# ProPrj.net
KiCad netlist of a schematic drawn in EasyEDA Pro
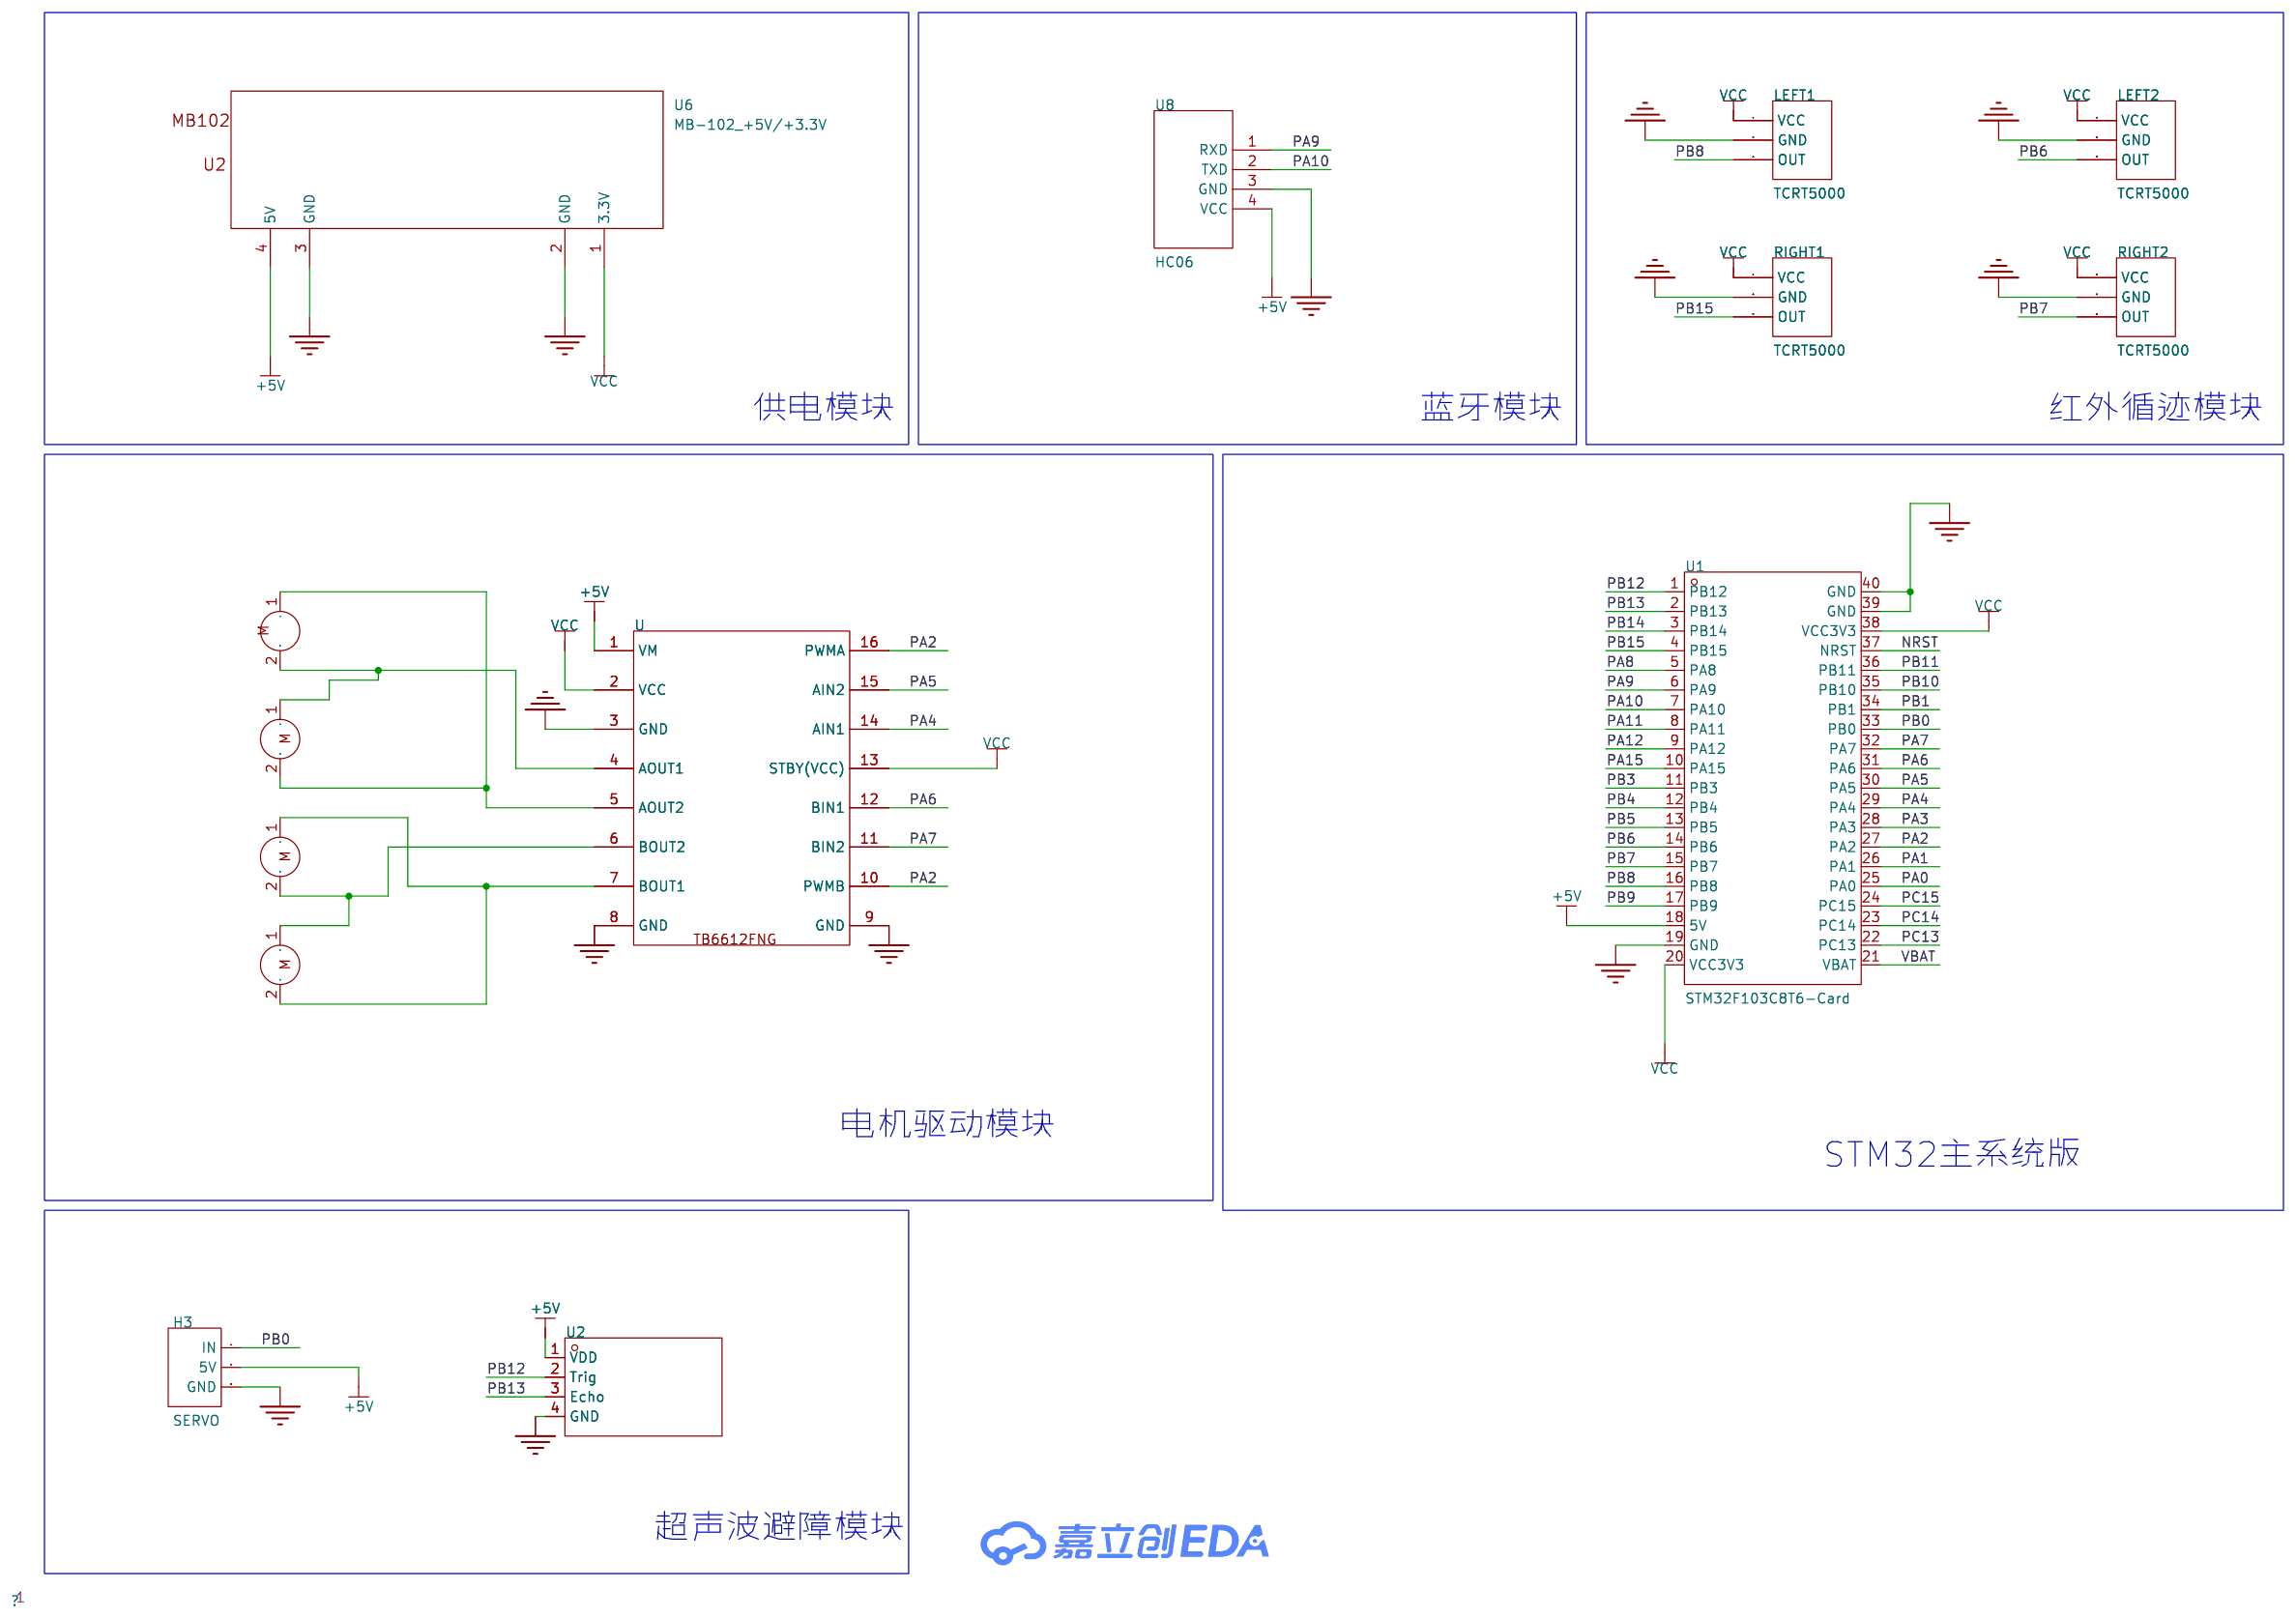
[diagram p0: schematic sheet]

(export (version "E")
  (design (tool "Eeschema 10.0.6"))
  (components
    (comp (ref "H3")
      (value "SERVO")
      (footprint "easyedapro:SERVO")
      (fields (field (name "Manufacturer Part") "Header2.54mm 1*3P") (field (name "Manufacturer") "BOOMELE"))
      (libsource (lib "easyedapro") (part "SERVO"))
    )
    (comp (ref "LEFT1")
      (value "TCRT5000")
      (footprint "easyedapro:footprint_0961")
      (libsource (lib "easyedapro") (part "TCRT5000"))
    )
    (comp (ref "LEFT2")
      (value "TCRT5000")
      (footprint "easyedapro:footprint_0961")
      (libsource (lib "easyedapro") (part "TCRT5000"))
    )
    (comp (ref "LEFT3")
      (value "DC 12V")
      (footprint "easyedapro:电源端子-2P")
      (libsource (lib "easyedapro") (part "直流电机"))
    )
    (comp (ref "LEFT4")
      (value "DC 12V")
      (footprint "easyedapro:电源端子-2P")
      (libsource (lib "easyedapro") (part "直流电机"))
    )
    (comp (ref "RIGHT1")
      (value "TCRT5000")
      (footprint "easyedapro:footprint_0961")
      (libsource (lib "easyedapro") (part "TCRT5000"))
    )
    (comp (ref "RIGHT2")
      (value "TCRT5000")
      (footprint "easyedapro:footprint_0961")
      (libsource (lib "easyedapro") (part "TCRT5000"))
    )
    (comp (ref "RIGHT3")
      (value "DC 12V")
      (footprint "easyedapro:电源端子-2P")
      (libsource (lib "easyedapro") (part "直流电机"))
    )
    (comp (ref "RIGHT4")
      (value "DC 12V")
      (footprint "easyedapro:电源端子-2P")
      (libsource (lib "easyedapro") (part "直流电机"))
    )
    (comp (ref "U")
      (value "~")
      (footprint "easyedapro:TB6612FNG")
      (libsource (lib "easyedapro") (part "TB6612"))
    )
    (comp (ref "U1")
      (value "STM32F103C8T6-Card")
      (footprint "easyedapro:CONN-TH_L53.3-W22.9_STM32F103C8T6-CARD")
      (libsource (lib "easyedapro") (part "STM32F103C8T6-CARD"))
    )
    (comp (ref "U2")
      (value "~")
      (footprint "easyedapro:HC-SR04")
      (libsource (lib "easyedapro") (part "HC-SR04"))
    )
    (comp (ref "U6")
      (value "MB-102_+5V/+3.3V")
      (footprint "easyedapro:MB-102_+5V/+3.3V")
      (libsource (lib "easyedapro") (part "MB-102_+5V/+3.3V"))
    )
    (comp (ref "U8")
      (value "HC06")
      (footprint "easyedapro:HC06")
      (libsource (lib "easyedapro") (part "HC06"))
    )
  )
  (nets
    (net (code "1") (name "+5V") (class "Default")
      (node (ref "H3") (pin "2") (pinfunction "5V_2") (pintype "input"))
      (node (ref "U") (pin "1") (pinfunction "VM_1") (pintype "input"))
      (node (ref "U1") (pin "18") (pinfunction "5V_18") (pintype "unspecified"))
      (node (ref "U2") (pin "1") (pinfunction "VDD_1") (pintype "input"))
      (node (ref "U6") (pin "4") (pinfunction "5V_4") (pintype "unspecified"))
      (node (ref "U8") (pin "4") (pinfunction "VCC_4") (pintype "unspecified"))
    )
    (net (code "2") (name "/NRST") (class "Default")
      (node (ref "U1") (pin "37") (pinfunction "NRST_37") (pintype "unspecified"))
    )
    (net (code "3") (name "/PA0") (class "Default")
      (node (ref "U1") (pin "25") (pinfunction "PA0_25") (pintype "unspecified"))
    )
    (net (code "4") (name "/PA1") (class "Default")
      (node (ref "U1") (pin "26") (pinfunction "PA1_26") (pintype "unspecified"))
    )
    (net (code "5") (name "/PA2") (class "Default")
      (node (ref "U") (pin "10") (pinfunction "PWMB_10") (pintype "input"))
      (node (ref "U") (pin "16") (pinfunction "PWMA_16") (pintype "input"))
      (node (ref "U1") (pin "27") (pinfunction "PA2_27") (pintype "unspecified"))
    )
    (net (code "6") (name "/PA3") (class "Default")
      (node (ref "U1") (pin "28") (pinfunction "PA3_28") (pintype "unspecified"))
    )
    (net (code "7") (name "/PA4") (class "Default")
      (node (ref "U") (pin "14") (pinfunction "AIN1_14") (pintype "input"))
      (node (ref "U1") (pin "29") (pinfunction "PA4_29") (pintype "unspecified"))
    )
    (net (code "8") (name "/PA5") (class "Default")
      (node (ref "U") (pin "15") (pinfunction "AIN2_15") (pintype "input"))
      (node (ref "U1") (pin "30") (pinfunction "PA5_30") (pintype "unspecified"))
    )
    (net (code "9") (name "/PA6") (class "Default")
      (node (ref "U") (pin "12") (pinfunction "BIN1_12") (pintype "input"))
      (node (ref "U1") (pin "31") (pinfunction "PA6_31") (pintype "unspecified"))
    )
    (net (code "10") (name "/PA7") (class "Default")
      (node (ref "U") (pin "11") (pinfunction "BIN2_11") (pintype "input"))
      (node (ref "U1") (pin "32") (pinfunction "PA7_32") (pintype "unspecified"))
    )
    (net (code "11") (name "/PA8") (class "Default")
      (node (ref "U1") (pin "5") (pinfunction "PA8_5") (pintype "unspecified"))
    )
    (net (code "12") (name "/PA9") (class "Default")
      (node (ref "U1") (pin "6") (pinfunction "PA9_6") (pintype "unspecified"))
      (node (ref "U8") (pin "1") (pinfunction "RXD_1") (pintype "unspecified"))
    )
    (net (code "13") (name "/PA10") (class "Default")
      (node (ref "U1") (pin "7") (pinfunction "PA10_7") (pintype "unspecified"))
      (node (ref "U8") (pin "2") (pinfunction "TXD_2") (pintype "unspecified"))
    )
    (net (code "14") (name "/PA11") (class "Default")
      (node (ref "U1") (pin "8") (pinfunction "PA11_8") (pintype "unspecified"))
    )
    (net (code "15") (name "/PA12") (class "Default")
      (node (ref "U1") (pin "9") (pinfunction "PA12_9") (pintype "unspecified"))
    )
    (net (code "16") (name "/PA15") (class "Default")
      (node (ref "U1") (pin "10") (pinfunction "PA15_10") (pintype "unspecified"))
    )
    (net (code "17") (name "/PB0") (class "Default")
      (node (ref "H3") (pin "1") (pinfunction "IN_1") (pintype "input"))
      (node (ref "U1") (pin "33") (pinfunction "PB0_33") (pintype "unspecified"))
    )
    (net (code "18") (name "/PB1") (class "Default")
      (node (ref "U1") (pin "34") (pinfunction "PB1_34") (pintype "unspecified"))
    )
    (net (code "19") (name "/PB3") (class "Default")
      (node (ref "U1") (pin "11") (pinfunction "PB3_11") (pintype "unspecified"))
    )
    (net (code "20") (name "/PB4") (class "Default")
      (node (ref "U1") (pin "12") (pinfunction "PB4_12") (pintype "unspecified"))
    )
    (net (code "21") (name "/PB5") (class "Default")
      (node (ref "U1") (pin "13") (pinfunction "PB5_13") (pintype "unspecified"))
    )
    (net (code "22") (name "/PB6") (class "Default")
      (node (ref "LEFT2") (pin "3") (pinfunction "OUT_3") (pintype "unspecified"))
      (node (ref "U1") (pin "14") (pinfunction "PB6_14") (pintype "unspecified"))
    )
    (net (code "23") (name "/PB7") (class "Default")
      (node (ref "RIGHT2") (pin "3") (pinfunction "OUT_3") (pintype "unspecified"))
      (node (ref "U1") (pin "15") (pinfunction "PB7_15") (pintype "unspecified"))
    )
    (net (code "24") (name "/PB8") (class "Default")
      (node (ref "LEFT1") (pin "3") (pinfunction "OUT_3") (pintype "unspecified"))
      (node (ref "U1") (pin "16") (pinfunction "PB8_16") (pintype "unspecified"))
    )
    (net (code "25") (name "/PB9") (class "Default")
      (node (ref "U1") (pin "17") (pinfunction "PB9_17") (pintype "unspecified"))
    )
    (net (code "26") (name "/PB10") (class "Default")
      (node (ref "U1") (pin "35") (pinfunction "PB10_35") (pintype "unspecified"))
    )
    (net (code "27") (name "/PB11") (class "Default")
      (node (ref "U1") (pin "36") (pinfunction "PB11_36") (pintype "unspecified"))
    )
    (net (code "28") (name "/PB12") (class "Default")
      (node (ref "U1") (pin "1") (pinfunction "PB12_1") (pintype "unspecified"))
      (node (ref "U2") (pin "2") (pinfunction "Trig_2") (pintype "input"))
    )
    (net (code "29") (name "/PB13") (class "Default")
      (node (ref "U1") (pin "2") (pinfunction "PB13_2") (pintype "unspecified"))
      (node (ref "U2") (pin "3") (pinfunction "Echo_3") (pintype "input"))
    )
    (net (code "30") (name "/PB14") (class "Default")
      (node (ref "U1") (pin "3") (pinfunction "PB14_3") (pintype "unspecified"))
    )
    (net (code "31") (name "/PB15") (class "Default")
      (node (ref "RIGHT1") (pin "3") (pinfunction "OUT_3") (pintype "unspecified"))
      (node (ref "U1") (pin "4") (pinfunction "PB15_4") (pintype "unspecified"))
    )
    (net (code "32") (name "/PC13") (class "Default")
      (node (ref "U1") (pin "22") (pinfunction "PC13_22") (pintype "unspecified"))
    )
    (net (code "33") (name "/PC14") (class "Default")
      (node (ref "U1") (pin "23") (pinfunction "PC14_23") (pintype "unspecified"))
    )
    (net (code "34") (name "/PC15") (class "Default")
      (node (ref "U1") (pin "24") (pinfunction "PC15_24") (pintype "unspecified"))
    )
    (net (code "35") (name "/VBAT") (class "Default")
      (node (ref "U1") (pin "21") (pinfunction "VBAT_21") (pintype "unspecified"))
    )
    (net (code "36") (name "GND") (class "Default")
      (node (ref "H3") (pin "3") (pinfunction "GND_3") (pintype "input"))
      (node (ref "LEFT1") (pin "2") (pinfunction "GND_2") (pintype "unspecified"))
      (node (ref "LEFT2") (pin "2") (pinfunction "GND_2") (pintype "unspecified"))
      (node (ref "RIGHT1") (pin "2") (pinfunction "GND_2") (pintype "unspecified"))
      (node (ref "RIGHT2") (pin "2") (pinfunction "GND_2") (pintype "unspecified"))
      (node (ref "U") (pin "3") (pinfunction "GND_3") (pintype "input"))
      (node (ref "U") (pin "8") (pinfunction "GND_8") (pintype "input"))
      (node (ref "U") (pin "9") (pinfunction "GND_9") (pintype "input"))
      (node (ref "U1") (pin "19") (pinfunction "GND_19") (pintype "unspecified"))
      (node (ref "U1") (pin "39") (pinfunction "GND_39") (pintype "unspecified"))
      (node (ref "U1") (pin "40") (pinfunction "GND_40") (pintype "unspecified"))
      (node (ref "U2") (pin "4") (pinfunction "GND_4") (pintype "input"))
      (node (ref "U6") (pin "2") (pinfunction "GND_2") (pintype "unspecified"))
      (node (ref "U6") (pin "3") (pinfunction "GND_3") (pintype "unspecified"))
      (node (ref "U8") (pin "3") (pinfunction "GND_3") (pintype "unspecified"))
    )
    (net (code "37") (name "Net-(U-AOUT1)") (class "Default")
      (node (ref "RIGHT3") (pin "2") (pinfunction "2_2") (pintype "input"))
      (node (ref "RIGHT4") (pin "1") (pinfunction "1_1") (pintype "input"))
      (node (ref "U") (pin "4") (pinfunction "AOUT1_4") (pintype "input"))
    )
    (net (code "38") (name "Net-(U-AOUT2)") (class "Default")
      (node (ref "RIGHT3") (pin "1") (pinfunction "1_1") (pintype "input"))
      (node (ref "RIGHT4") (pin "2") (pinfunction "2_2") (pintype "input"))
      (node (ref "U") (pin "5") (pinfunction "AOUT2_5") (pintype "input"))
    )
    (net (code "39") (name "Net-(U-BOUT1)") (class "Default")
      (node (ref "LEFT3") (pin "1") (pinfunction "1_1") (pintype "input"))
      (node (ref "LEFT4") (pin "2") (pinfunction "2_2") (pintype "input"))
      (node (ref "U") (pin "7") (pinfunction "BOUT1_7") (pintype "input"))
    )
    (net (code "40") (name "Net-(U-BOUT2)") (class "Default")
      (node (ref "LEFT3") (pin "2") (pinfunction "2_2") (pintype "input"))
      (node (ref "LEFT4") (pin "1") (pinfunction "1_1") (pintype "input"))
      (node (ref "U") (pin "6") (pinfunction "BOUT2_6") (pintype "input"))
    )
    (net (code "41") (name "VCC") (class "Default")
      (node (ref "LEFT1") (pin "1") (pinfunction "VCC_1") (pintype "unspecified"))
      (node (ref "LEFT2") (pin "1") (pinfunction "VCC_1") (pintype "unspecified"))
      (node (ref "RIGHT1") (pin "1") (pinfunction "VCC_1") (pintype "unspecified"))
      (node (ref "RIGHT2") (pin "1") (pinfunction "VCC_1") (pintype "unspecified"))
      (node (ref "U") (pin "13") (pinfunction "STBY(VCC)_13") (pintype "input"))
      (node (ref "U") (pin "2") (pinfunction "VCC_2") (pintype "input"))
      (node (ref "U1") (pin "20") (pinfunction "VCC3V3_20") (pintype "unspecified"))
      (node (ref "U1") (pin "38") (pinfunction "VCC3V3_38") (pintype "unspecified"))
      (node (ref "U6") (pin "1") (pinfunction "3.3V_1") (pintype "unspecified"))
    )
  )
)
